# VCO.net
KiCad netlist of a schematic drawn in EAGLE
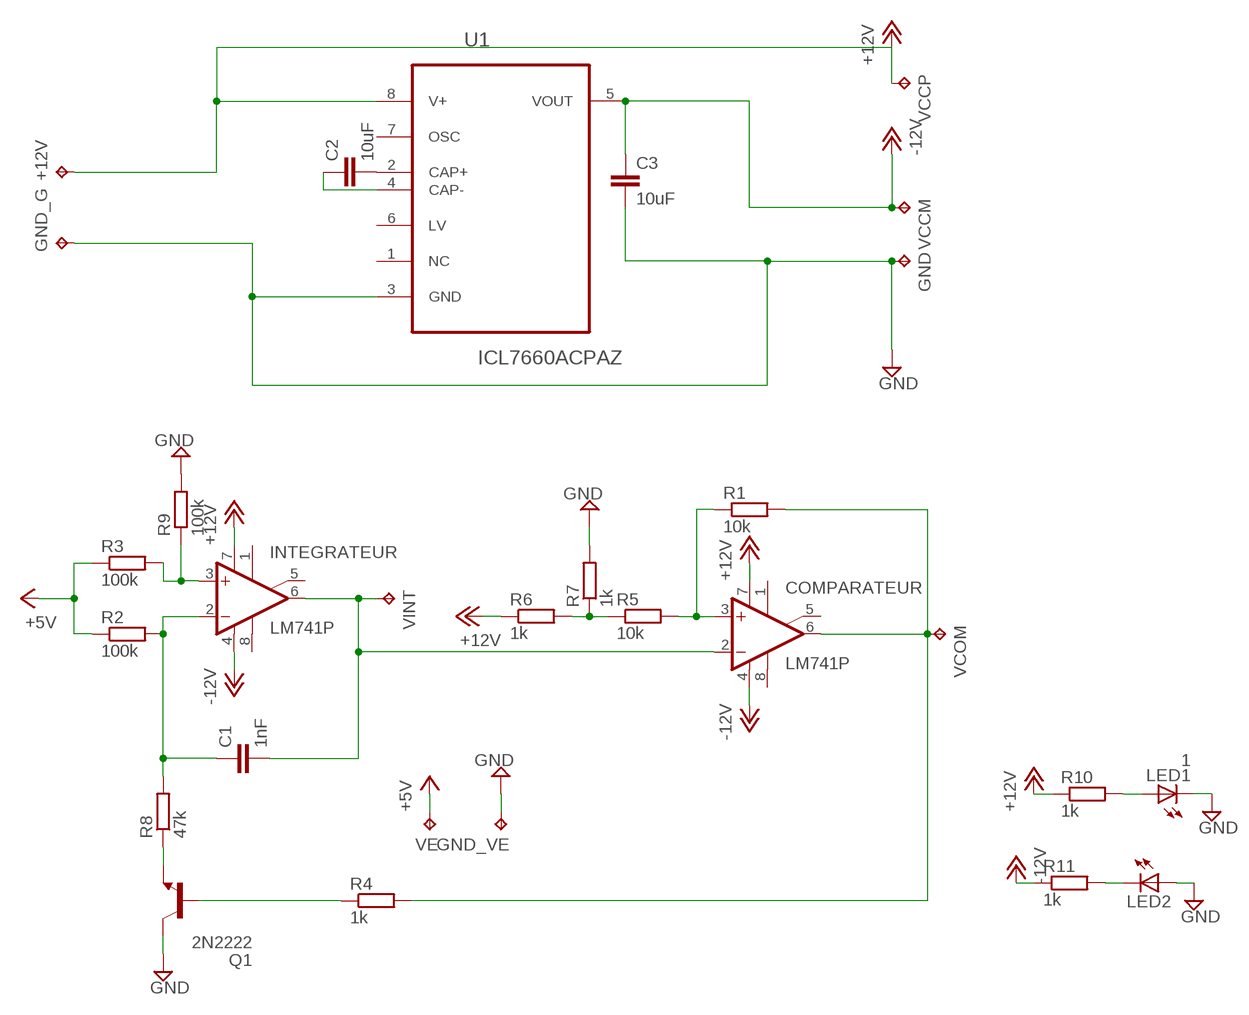
[diagram p0: schematic, sheet 1]

(export (version "E")
  (design (tool "Eeschema 10.0.6"))
  (components
    (comp (ref "+12V")
      (value "TPPAD1-13")
      (footprint "eagle-import:P1-13")
      (libsource (lib "eagle-import") (part "TPPAD1-13"))
    )
    (comp (ref "C1")
      (value "1nF")
      (footprint "eagle-import:C050-025X075")
      (libsource (lib "eagle-import") (part "C050-025X075"))
    )
    (comp (ref "C2")
      (value "10uF")
      (footprint "eagle-import:C050-025X075")
      (libsource (lib "eagle-import") (part "C050-025X075"))
    )
    (comp (ref "C3")
      (value "10uF")
      (footprint "eagle-import:C050-025X075")
      (libsource (lib "eagle-import") (part "C050-025X075"))
    )
    (comp (ref "COMPARATEUR")
      (value "LM741P")
      (footprint "eagle-import:DIL08")
      (libsource (lib "eagle-import") (part "741PLM"))
    )
    (comp (ref "GND")
      (value "TPPAD1-13")
      (footprint "eagle-import:P1-13")
      (libsource (lib "eagle-import") (part "TPPAD1-13"))
    )
    (comp (ref "GND_G")
      (value "TPPAD1-13")
      (footprint "eagle-import:P1-13")
      (libsource (lib "eagle-import") (part "TPPAD1-13"))
    )
    (comp (ref "GND_VE")
      (value "TPPAD1-13")
      (footprint "eagle-import:P1-13")
      (libsource (lib "eagle-import") (part "TPPAD1-13"))
    )
    (comp (ref "INTEGRATEUR")
      (value "LM741P")
      (footprint "eagle-import:DIL08")
      (libsource (lib "eagle-import") (part "741PLM"))
    )
    (comp (ref "LED1")
      (value "1")
      (footprint "eagle-import:LED5MM")
      (libsource (lib "eagle-import") (part "LED5MM"))
    )
    (comp (ref "LED2")
      (value "LED5MM")
      (footprint "eagle-import:LED5MM")
      (libsource (lib "eagle-import") (part "LED5MM"))
    )
    (comp (ref "Q1")
      (value "2N2222")
      (footprint "eagle-import:TO18")
      (libsource (lib "eagle-import") (part "2N2222"))
    )
    (comp (ref "R1")
      (value "10k")
      (footprint "eagle-import:0204_7")
      (libsource (lib "eagle-import") (part "R0204/7"))
    )
    (comp (ref "R2")
      (value "100k")
      (footprint "eagle-import:0204_7")
      (libsource (lib "eagle-import") (part "R0204/7"))
    )
    (comp (ref "R3")
      (value "100k")
      (footprint "eagle-import:0204_7")
      (libsource (lib "eagle-import") (part "R0204/7"))
    )
    (comp (ref "R4")
      (value "1k")
      (footprint "eagle-import:0204_7")
      (libsource (lib "eagle-import") (part "R0204/7"))
    )
    (comp (ref "R5")
      (value "10k")
      (footprint "eagle-import:0204_7")
      (libsource (lib "eagle-import") (part "R0204/7"))
    )
    (comp (ref "R6")
      (value "1k")
      (footprint "eagle-import:0204_7")
      (libsource (lib "eagle-import") (part "R0204/7"))
    )
    (comp (ref "R7")
      (value "1k")
      (footprint "eagle-import:0204_7")
      (libsource (lib "eagle-import") (part "R0204/7"))
    )
    (comp (ref "R8")
      (value "47k")
      (footprint "eagle-import:0204_7")
      (libsource (lib "eagle-import") (part "R0204/7"))
    )
    (comp (ref "R9")
      (value "100k")
      (footprint "eagle-import:0204_7")
      (libsource (lib "eagle-import") (part "R0204/7"))
    )
    (comp (ref "R10")
      (value "1k")
      (footprint "eagle-import:0204_7")
      (libsource (lib "eagle-import") (part "R0204/7"))
    )
    (comp (ref "R11")
      (value "1k")
      (footprint "eagle-import:0204_7")
      (libsource (lib "eagle-import") (part "R0204/7"))
    )
    (comp (ref "U1")
      (value "ICL7660ACPAZ")
      (footprint "eagle-import:DIP254P762X533-8")
      (libsource (lib "eagle-import") (part "ICL7660ACPAZ"))
    )
    (comp (ref "VCCM")
      (value "TPPAD1-13")
      (footprint "eagle-import:P1-13")
      (libsource (lib "eagle-import") (part "TPPAD1-13"))
    )
    (comp (ref "VCCP")
      (value "TPPAD1-13")
      (footprint "eagle-import:P1-13")
      (libsource (lib "eagle-import") (part "TPPAD1-13"))
    )
    (comp (ref "VCOM")
      (value "TPPAD1-13")
      (footprint "eagle-import:P1-13")
      (libsource (lib "eagle-import") (part "TPPAD1-13"))
    )
    (comp (ref "VE")
      (value "TPPAD1-13")
      (footprint "eagle-import:P1-13")
      (libsource (lib "eagle-import") (part "TPPAD1-13"))
    )
    (comp (ref "VINT")
      (value "TPPAD1-13")
      (footprint "eagle-import:P1-13")
      (libsource (lib "eagle-import") (part "TPPAD1-13"))
    )
  )
  (nets
    (net (code "1") (name "+5V") (class "Default")
      (node (ref "R2") (pin "1") (pinfunction "1_1") (pintype "passive"))
      (node (ref "R3") (pin "1") (pinfunction "1_1") (pintype "passive"))
      (node (ref "VE") (pin "TP") (pinfunction "TP_TP") (pintype "input"))
    )
    (net (code "2") (name "+12V") (class "Default")
      (node (ref "+12V") (pin "TP") (pinfunction "TP_TP") (pintype "input"))
      (node (ref "COMPARATEUR") (pin "7") (pinfunction "V+_7") (pintype "power_in"))
      (node (ref "INTEGRATEUR") (pin "7") (pinfunction "V+_7") (pintype "power_in"))
      (node (ref "R10") (pin "1") (pinfunction "1_1") (pintype "passive"))
      (node (ref "R6") (pin "1") (pinfunction "1_1") (pintype "passive"))
      (node (ref "U1") (pin "8") (pinfunction "V+_8") (pintype "power_in"))
      (node (ref "VCCP") (pin "TP") (pinfunction "TP_TP") (pintype "input"))
    )
    (net (code "3") (name "-12V") (class "Default")
      (node (ref "C3") (pin "1") (pinfunction "1_1") (pintype "passive"))
      (node (ref "COMPARATEUR") (pin "4") (pinfunction "V-_4") (pintype "power_in"))
      (node (ref "INTEGRATEUR") (pin "4") (pinfunction "V-_4") (pintype "power_in"))
      (node (ref "R11") (pin "1") (pinfunction "1_1") (pintype "passive"))
      (node (ref "U1") (pin "5") (pinfunction "VOUT_5") (pintype "output"))
      (node (ref "VCCM") (pin "TP") (pinfunction "TP_TP") (pintype "input"))
    )
    (net (code "4") (name "GND") (class "Default")
      (node (ref "C3") (pin "2") (pinfunction "2_2") (pintype "passive"))
      (node (ref "GND") (pin "TP") (pinfunction "TP_TP") (pintype "input"))
      (node (ref "GND_G") (pin "TP") (pinfunction "TP_TP") (pintype "input"))
      (node (ref "GND_VE") (pin "TP") (pinfunction "TP_TP") (pintype "input"))
      (node (ref "LED1") (pin "K") (pinfunction "C_K") (pintype "passive"))
      (node (ref "LED2") (pin "A") (pinfunction "A_A") (pintype "passive"))
      (node (ref "Q1") (pin "3") (pinfunction "C_3") (pintype "passive"))
      (node (ref "R7") (pin "2") (pinfunction "2_2") (pintype "passive"))
      (node (ref "R9") (pin "2") (pinfunction "2_2") (pintype "passive"))
      (node (ref "U1") (pin "3") (pinfunction "GND_3") (pintype "passive"))
    )
    (net (code "5") (name "Net-(COMPARATEUR-+IN)") (class "Default")
      (node (ref "COMPARATEUR") (pin "3") (pinfunction "+IN_3") (pintype "input"))
      (node (ref "R1") (pin "1") (pinfunction "1_1") (pintype "passive"))
      (node (ref "R5") (pin "2") (pinfunction "2_2") (pintype "passive"))
    )
    (net (code "6") (name "Net-(COMPARATEUR--IN)") (class "Default")
      (node (ref "C1") (pin "2") (pinfunction "2_2") (pintype "passive"))
      (node (ref "COMPARATEUR") (pin "2") (pinfunction "-IN_2") (pintype "input"))
      (node (ref "INTEGRATEUR") (pin "6") (pinfunction "OUT_6") (pintype "output"))
      (node (ref "VINT") (pin "TP") (pinfunction "TP_TP") (pintype "input"))
    )
    (net (code "7") (name "Net-(COMPARATEUR-OUT)") (class "Default")
      (node (ref "COMPARATEUR") (pin "6") (pinfunction "OUT_6") (pintype "output"))
      (node (ref "R1") (pin "2") (pinfunction "2_2") (pintype "passive"))
      (node (ref "R4") (pin "2") (pinfunction "2_2") (pintype "passive"))
      (node (ref "VCOM") (pin "TP") (pinfunction "TP_TP") (pintype "input"))
    )
    (net (code "8") (name "Net-(INTEGRATEUR-+IN)") (class "Default")
      (node (ref "INTEGRATEUR") (pin "3") (pinfunction "+IN_3") (pintype "input"))
      (node (ref "R3") (pin "2") (pinfunction "2_2") (pintype "passive"))
      (node (ref "R9") (pin "1") (pinfunction "1_1") (pintype "passive"))
    )
    (net (code "9") (name "Net-(INTEGRATEUR--IN)") (class "Default")
      (node (ref "C1") (pin "1") (pinfunction "1_1") (pintype "passive"))
      (node (ref "INTEGRATEUR") (pin "2") (pinfunction "-IN_2") (pintype "input"))
      (node (ref "R2") (pin "2") (pinfunction "2_2") (pintype "passive"))
      (node (ref "R8") (pin "2") (pinfunction "2_2") (pintype "passive"))
    )
    (net (code "10") (name "Net-(LED1-PadA)") (class "Default")
      (node (ref "LED1") (pin "A") (pinfunction "A_A") (pintype "passive"))
      (node (ref "R10") (pin "2") (pinfunction "2_2") (pintype "passive"))
    )
    (net (code "11") (name "Net-(LED2-C)") (class "Default")
      (node (ref "LED2") (pin "K") (pinfunction "C_K") (pintype "passive"))
      (node (ref "R11") (pin "2") (pinfunction "2_2") (pintype "passive"))
    )
    (net (code "12") (name "Net-(Q1-B)") (class "Default")
      (node (ref "Q1") (pin "2") (pinfunction "B_2") (pintype "passive"))
      (node (ref "R4") (pin "1") (pinfunction "1_1") (pintype "passive"))
    )
    (net (code "13") (name "Net-(Q1-E)") (class "Default")
      (node (ref "Q1") (pin "1") (pinfunction "E_1") (pintype "passive"))
      (node (ref "R8") (pin "1") (pinfunction "1_1") (pintype "passive"))
    )
    (net (code "14") (name "Net-(R5-Pad1)") (class "Default")
      (node (ref "R5") (pin "1") (pinfunction "1_1") (pintype "passive"))
      (node (ref "R6") (pin "2") (pinfunction "2_2") (pintype "passive"))
      (node (ref "R7") (pin "1") (pinfunction "1_1") (pintype "passive"))
    )
    (net (code "15") (name "Net-(U1-CAP+)") (class "Default")
      (node (ref "C2") (pin "2") (pinfunction "2_2") (pintype "passive"))
      (node (ref "U1") (pin "2") (pinfunction "CAP+_2") (pintype "input"))
    )
    (net (code "16") (name "Net-(U1-CAP-)") (class "Default")
      (node (ref "C2") (pin "1") (pinfunction "1_1") (pintype "passive"))
      (node (ref "U1") (pin "4") (pinfunction "CAP-_4") (pintype "input"))
    )
    (net (code "17") (name "unconnected-(COMPARATEUR-ON1-Pad1)") (class "Default")
      (node (ref "COMPARATEUR") (pin "1") (pinfunction "ON1_1") (pintype "passive"))
    )
    (net (code "18") (name "unconnected-(COMPARATEUR-ON2-Pad5)") (class "Default")
      (node (ref "COMPARATEUR") (pin "5") (pinfunction "ON2_5") (pintype "passive"))
    )
    (net (code "19") (name "unconnected-(COMPARATEUR-OPT-Pad8)") (class "Default")
      (node (ref "COMPARATEUR") (pin "8") (pinfunction "OPT_8") (pintype "passive"))
    )
    (net (code "20") (name "unconnected-(INTEGRATEUR-ON1-Pad1)") (class "Default")
      (node (ref "INTEGRATEUR") (pin "1") (pinfunction "ON1_1") (pintype "passive"))
    )
    (net (code "21") (name "unconnected-(INTEGRATEUR-ON2-Pad5)") (class "Default")
      (node (ref "INTEGRATEUR") (pin "5") (pinfunction "ON2_5") (pintype "passive"))
    )
    (net (code "22") (name "unconnected-(INTEGRATEUR-OPT-Pad8)") (class "Default")
      (node (ref "INTEGRATEUR") (pin "8") (pinfunction "OPT_8") (pintype "passive"))
    )
    (net (code "23") (name "unconnected-(U1-LV-Pad6)") (class "Default")
      (node (ref "U1") (pin "6") (pinfunction "LV_6") (pintype "passive"))
    )
    (net (code "24") (name "unconnected-(U1-NC-Pad1)") (class "Default")
      (node (ref "U1") (pin "1") (pinfunction "NC_1") (pintype "no_connect"))
    )
    (net (code "25") (name "unconnected-(U1-OSC-Pad7)") (class "Default")
      (node (ref "U1") (pin "7") (pinfunction "OSC_7") (pintype "input"))
    )
  )
)
